# SD_Card.net
KiCad netlist of a schematic drawn in Altium Designer
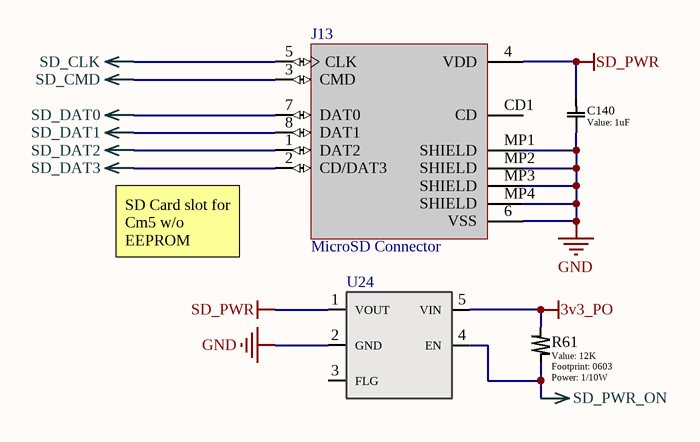
[diagram p0: SD_Card.SchDoc]

(export (version "E")
  (design (tool "Eeschema 10.0.6"))
  (components
    (comp (ref "C140")
      (value "1uF")
      (footprint "0603")
      (fields
        (field (name "VOLTAGE") "6V")
        (field (name "TOLERANCE") "5%")
        (field (name "Comment") "Generic Capacitor")
      )
      (libsource (lib "Capacitors") (part "Generic Capacitor"))
    )
    (comp (ref "J13")
      (value "MicroSD Connector")
      (footprint "TF-01A - NoCut")
      (description "Deck MicroSD card (TF card) Self bomb SMD SD Card Connector")
      (libsource (lib "Connectors") (part "TF-01A"))
    )
    (comp (ref "R61")
      (value "12K")
      (footprint "0603")
      (fields
        (field (name "TOLERANCE") "1%")
        (field (name "POWER") "1/10W")
        (field (name "Comment") "Generic Resistor")
      )
      (libsource (lib "Resistors") (part "Generic Resistor"))
    )
    (comp (ref "U24")
      (value "~")
      (footprint "TSOT-23-5")
      (description "Power Switch/Driver 1:1 N-Channel 1A TSOT-23-5")
      (libsource (lib "Switches") (part "RT9742GGJ5"))
    )
  )
  (nets
    (net (code "1") (name "3v3_PO") (class "Default")
      (node (ref "R61") (pin "1") (pinfunction "1_1") (pintype "passive"))
      (node (ref "U24") (pin "5") (pinfunction "VIN_5") (pintype "passive"))
    )
    (net (code "2") (name "GND") (class "Default")
      (node (ref "C140") (pin "1") (pinfunction "1_1") (pintype "passive"))
      (node (ref "J13") (pin "6") (pinfunction "VSS_6") (pintype "power_in"))
      (node (ref "J13") (pin "MP1") (pinfunction "SHIELD_MP1") (pintype "power_in"))
      (node (ref "J13") (pin "MP2") (pinfunction "SHIELD_MP2") (pintype "power_in"))
      (node (ref "J13") (pin "MP3") (pinfunction "SHIELD_MP3") (pintype "power_in"))
      (node (ref "J13") (pin "MP4") (pinfunction "SHIELD_MP4") (pintype "power_in"))
      (node (ref "U24") (pin "2") (pinfunction "GND_2") (pintype "passive"))
    )
    (net (code "3") (name "SD_CLK") (class "Default")
      (node (ref "J13") (pin "5") (pinfunction "CLK_5") (pintype "bidirectional"))
    )
    (net (code "4") (name "SD_CMD") (class "Default")
      (node (ref "J13") (pin "3") (pinfunction "CMD_3") (pintype "bidirectional"))
    )
    (net (code "5") (name "SD_DAT0") (class "Default")
      (node (ref "J13") (pin "7") (pinfunction "DAT0_7") (pintype "bidirectional"))
    )
    (net (code "6") (name "SD_DAT1") (class "Default")
      (node (ref "J13") (pin "8") (pinfunction "DAT1_8") (pintype "bidirectional"))
    )
    (net (code "7") (name "SD_DAT2") (class "Default")
      (node (ref "J13") (pin "1") (pinfunction "DAT2_1") (pintype "bidirectional"))
    )
    (net (code "8") (name "SD_DAT3") (class "Default")
      (node (ref "J13") (pin "2") (pinfunction "CD/DAT3_2") (pintype "bidirectional"))
    )
    (net (code "9") (name "SD_PWR") (class "Default")
      (node (ref "C140") (pin "2") (pinfunction "2_2") (pintype "passive"))
      (node (ref "J13") (pin "4") (pinfunction "VDD_4") (pintype "power_in"))
      (node (ref "U24") (pin "1") (pinfunction "VOUT_1") (pintype "passive"))
    )
    (net (code "10") (name "SD_PWR_ON") (class "Default")
      (node (ref "R61") (pin "2") (pinfunction "2_2") (pintype "passive"))
      (node (ref "U24") (pin "4") (pinfunction "EN_4") (pintype "passive"))
    )
    (net (code "11") (name "unconnected-(J13-CD-PadCD1)") (class "Default")
      (node (ref "J13") (pin "CD1") (pinfunction "CD_CD1") (pintype "passive"))
    )
    (net (code "12") (name "unconnected-(U24-FLG-Pad3)") (class "Default")
      (node (ref "U24") (pin "3") (pinfunction "FLG_3") (pintype "passive"))
    )
  )
)
